# ESP32-Function.net
KiCad netlist of a schematic drawn in EAGLE
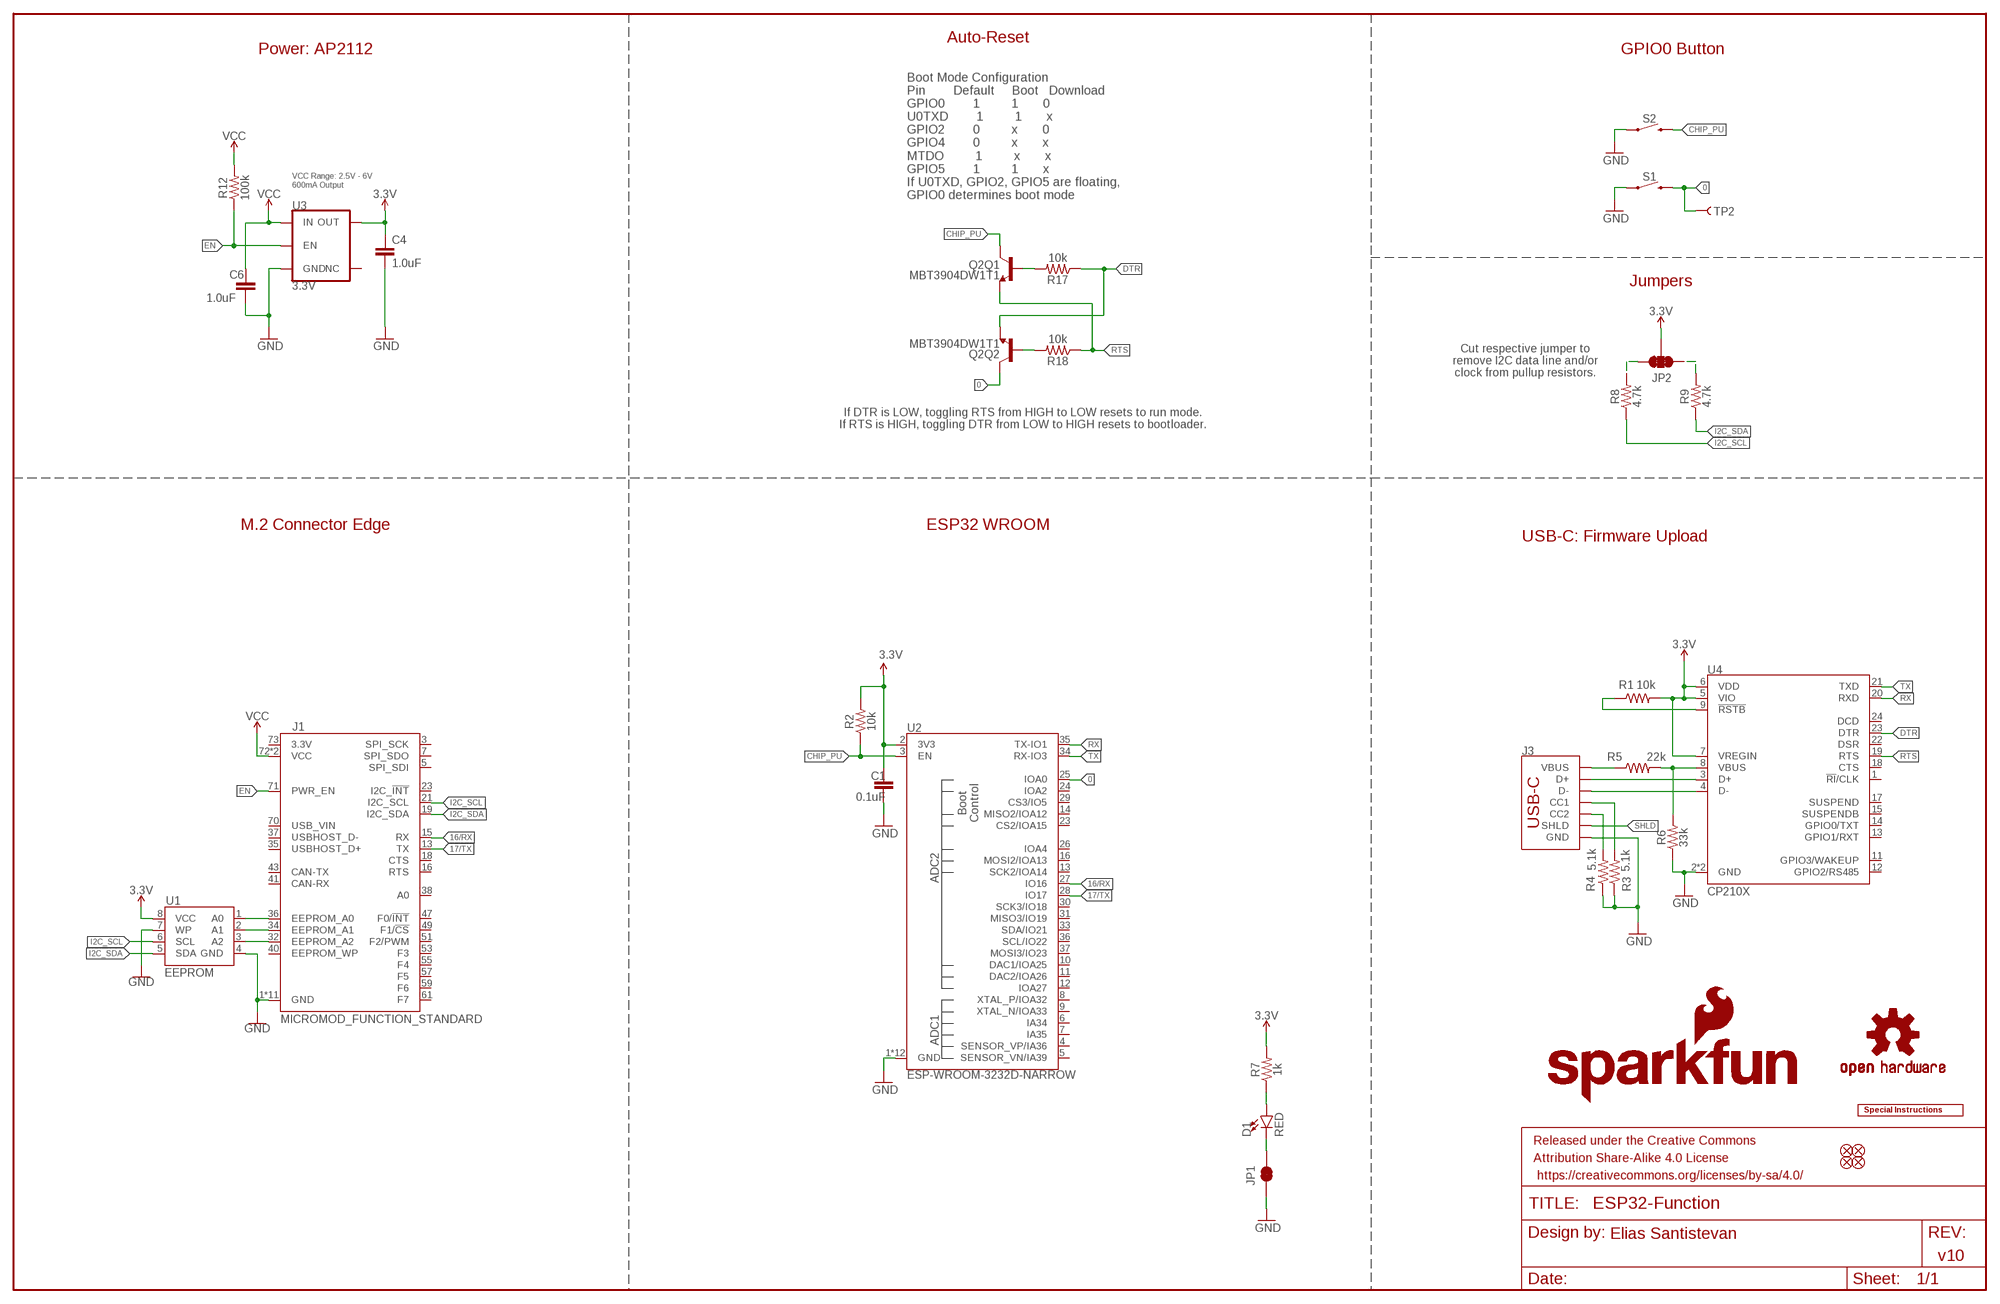
[diagram p0: schematic, sheet 1]

(export (version "E")
  (design (tool "Eeschema 10.0.6"))
  (components
    (comp (ref "C1")
      (value "0.1uF")
      (footprint "eagle-import:0603")
      (libsource (lib "eagle-import") (part "0.1UF-0603-25V-(+80/-20%)"))
    )
    (comp (ref "C4")
      (value "1.0uF")
      (footprint "eagle-import:0603")
      (libsource (lib "eagle-import") (part "1.0UF-0603-16V-10%"))
    )
    (comp (ref "C6")
      (value "1.0uF")
      (footprint "eagle-import:0603")
      (libsource (lib "eagle-import") (part "1.0UF-0603-16V-10%"))
    )
    (comp (ref "D1")
      (value "RED")
      (footprint "eagle-import:LED-0603")
      (libsource (lib "eagle-import") (part "LED-RED0603"))
    )
    (comp (ref "FD1")
      (value "FIDUCIAL1X2")
      (footprint "eagle-import:FIDUCIAL-1X2")
      (libsource (lib "eagle-import") (part "FIDUCIAL1X2"))
    )
    (comp (ref "FD2")
      (value "FIDUCIAL1X2")
      (footprint "eagle-import:FIDUCIAL-1X2")
      (libsource (lib "eagle-import") (part "FIDUCIAL1X2"))
    )
    (comp (ref "FD3")
      (value "FIDUCIAL1X2")
      (footprint "eagle-import:FIDUCIAL-1X2")
      (libsource (lib "eagle-import") (part "FIDUCIAL1X2"))
    )
    (comp (ref "FD4")
      (value "FIDUCIAL1X2")
      (footprint "eagle-import:FIDUCIAL-1X2")
      (libsource (lib "eagle-import") (part "FIDUCIAL1X2"))
    )
    (comp (ref "FRAME2")
      (value "FRAME-LEDGER")
      (footprint "eagle-import:CREATIVE_COMMONS")
      (libsource (lib "eagle-import") (part "FRAME-LEDGER"))
    )
    (comp (ref "J1")
      (value "MICROMOD_FUNCTION_STANDARD")
      (footprint "eagle-import:M.2-CARD-E-22_FUNCTION_STANDARD")
      (libsource (lib "eagle-import") (part "MICROMOD_FUNCTION_STANDARD"))
    )
    (comp (ref "J3")
      (value "USB_C_2-LAYER_PADS")
      (footprint "eagle-import:USB-C-16P-2LAYER-PADS")
      (libsource (lib "eagle-import") (part "USB_C_2-LAYER_PADS"))
    )
    (comp (ref "JP1")
      (value "JUMPER-SMT_2_NC_TRACE_SILK")
      (footprint "eagle-import:SMT-JUMPER_2_NC_TRACE_SILK")
      (libsource (lib "eagle-import") (part "JUMPER-SMT_2_NC_TRACE_SILK"))
    )
    (comp (ref "JP2")
      (value "JUMPER-SMT_3_2-NC_TRACE_SILK")
      (footprint "eagle-import:SMT-JUMPER_3_2-NC_TRACE_SILK")
      (libsource (lib "eagle-import") (part "JUMPER-SMT_3_2-NC_TRACE_SILK"))
    )
    (comp (ref "LOGO1")
      (value "SPECIAL_INSTRUCTIONS-ORDERING")
      (footprint "eagle-import:ORDERING_INSTRUCTIONS")
      (libsource (lib "eagle-import") (part "SPECIAL_INSTRUCTIONS-ORDERING"))
    )
    (comp (ref "LOGO2")
      (value "SFE_LOGO_NAME_FLAME.2_INCH")
      (footprint "eagle-import:SFE_LOGO_NAME_FLAME_.2")
      (libsource (lib "eagle-import") (part "SFE_LOGO_NAME_FLAME.2_INCH"))
    )
    (comp (ref "LOGO3")
      (value "OSHW-LOGOS")
      (footprint "eagle-import:OSHW-LOGO-S")
      (libsource (lib "eagle-import") (part "OSHW-LOGOS"))
    )
    (comp (ref "Q2")
      (value "MBT3904DW1T1")
      (footprint "eagle-import:SC70-6")
      (libsource (lib "eagle-import") (part "TRANS_NPN_DUAL-MBT3904DW1T1"))
    )
    (comp (ref "R1")
      (value "10k")
      (footprint "eagle-import:0603")
      (libsource (lib "eagle-import") (part "10KOHM-0603-1/10W-1%"))
    )
    (comp (ref "R2")
      (value "10k")
      (footprint "eagle-import:0603")
      (libsource (lib "eagle-import") (part "10KOHM-0603-1/10W-1%"))
    )
    (comp (ref "R3")
      (value "5.1k")
      (footprint "eagle-import:0603")
      (libsource (lib "eagle-import") (part "5.1KOHM5.1KOHM-0603-1/10W-1%"))
    )
    (comp (ref "R4")
      (value "5.1k")
      (footprint "eagle-import:0603")
      (libsource (lib "eagle-import") (part "5.1KOHM5.1KOHM-0603-1/10W-1%"))
    )
    (comp (ref "R5")
      (value "22k")
      (footprint "eagle-import:0603")
      (libsource (lib "eagle-import") (part "22KOHM-0603-1/10W-1%"))
    )
    (comp (ref "R6")
      (value "33k")
      (footprint "eagle-import:0603")
      (libsource (lib "eagle-import") (part "33KOHM-0603-1/10W-1%"))
    )
    (comp (ref "R7")
      (value "1k")
      (footprint "eagle-import:0603")
      (libsource (lib "eagle-import") (part "1KOHM-0603-1/10W-1%"))
    )
    (comp (ref "R8")
      (value "4.7k")
      (footprint "eagle-import:0603")
      (libsource (lib "eagle-import") (part "4.7KOHM-0603-1/10W-1%"))
    )
    (comp (ref "R9")
      (value "4.7k")
      (footprint "eagle-import:0603")
      (libsource (lib "eagle-import") (part "4.7KOHM-0603-1/10W-1%"))
    )
    (comp (ref "R12")
      (value "100k")
      (footprint "eagle-import:0603")
      (libsource (lib "eagle-import") (part "100KOHM-0603-1/10W-1%"))
    )
    (comp (ref "R17")
      (value "10k")
      (footprint "eagle-import:0603")
      (libsource (lib "eagle-import") (part "10KOHM-0603-1/10W-1%"))
    )
    (comp (ref "R18")
      (value "10k")
      (footprint "eagle-import:0603")
      (libsource (lib "eagle-import") (part "10KOHM-0603-1/10W-1%"))
    )
    (comp (ref "S1")
      (value "MOMENTARY-SWITCH-SPST-SMD-5.2MM-TALL")
      (footprint "eagle-import:TACTILE_SWITCH_SMD_5.2MM")
      (libsource (lib "eagle-import") (part "MOMENTARY-SWITCH-SPST-SMD-5.2MM-TALL"))
    )
    (comp (ref "S2")
      (value "MOMENTARY-SWITCH-SPST-SMD-5.2MM-TALL")
      (footprint "eagle-import:TACTILE_SWITCH_SMD_5.2MM")
      (libsource (lib "eagle-import") (part "MOMENTARY-SWITCH-SPST-SMD-5.2MM-TALL"))
    )
    (comp (ref "TP2")
      (value "TEST-POINTTP_15TH_THRU")
      (footprint "eagle-import:TP_15TH")
      (libsource (lib "eagle-import") (part "TEST-POINTTP_15TH_THRU"))
    )
    (comp (ref "U1")
      (value "EEPROM")
      (footprint "eagle-import:SO08")
      (libsource (lib "eagle-import") (part "EEPROM-I2C512K"))
    )
    (comp (ref "U2")
      (value "ESP-WROOM-3232D-NARROW")
      (footprint "eagle-import:ESP-WROOM-32D-NARROW")
      (libsource (lib "eagle-import") (part "ESP-WROOM-3232D-NARROW"))
    )
    (comp (ref "U3")
      (value "3.3V")
      (footprint "eagle-import:SOT23-5")
      (libsource (lib "eagle-import") (part "V_REG_AP2112K-3.3V"))
    )
    (comp (ref "U4")
      (value "CP210X")
      (footprint "eagle-import:QFN24")
      (libsource (lib "eagle-import") (part "CP2102N"))
    )
  )
  (nets
    (net (code "1") (name "0") (class "Default")
      (node (ref "Q2") (pin "6") (pinfunction "C_6") (pintype "passive"))
      (node (ref "S1") (pin "3") (pinfunction "2_3") (pintype "passive"))
      (node (ref "TP2") (pin "1") (pinfunction "1_1") (pintype "bidirectional"))
      (node (ref "U2") (pin "25") (pinfunction "IOA0_25") (pintype "bidirectional"))
    )
    (net (code "2") (name "3.3V") (class "Default")
      (node (ref "C1") (pin "1") (pinfunction "1_1") (pintype "passive"))
      (node (ref "C4") (pin "1") (pinfunction "1_1") (pintype "passive"))
      (node (ref "JP2") (pin "2") (pinfunction "2_2") (pintype "passive"))
      (node (ref "R1") (pin "2") (pinfunction "2_2") (pintype "passive"))
      (node (ref "R2") (pin "2") (pinfunction "2_2") (pintype "passive"))
      (node (ref "R7") (pin "2") (pinfunction "2_2") (pintype "passive"))
      (node (ref "U1") (pin "8") (pinfunction "VCC_8") (pintype "power_in"))
      (node (ref "U2") (pin "2") (pinfunction "3V3_2") (pintype "bidirectional"))
      (node (ref "U3") (pin "5") (pinfunction "OUT_5") (pintype "passive"))
      (node (ref "U4") (pin "5") (pinfunction "VIO_5") (pintype "bidirectional"))
      (node (ref "U4") (pin "6") (pinfunction "VDD_6") (pintype "bidirectional"))
      (node (ref "U4") (pin "7") (pinfunction "VREGIN_7") (pintype "bidirectional"))
    )
    (net (code "3") (name "16{slash}RX") (class "Default")
      (node (ref "J1") (pin "15") (pinfunction "RX_15") (pintype "bidirectional"))
      (node (ref "U2") (pin "27") (pinfunction "IO16_27") (pintype "bidirectional"))
    )
    (net (code "4") (name "17{slash}TX") (class "Default")
      (node (ref "J1") (pin "13") (pinfunction "TX_13") (pintype "bidirectional"))
      (node (ref "U2") (pin "28") (pinfunction "IO17_28") (pintype "bidirectional"))
    )
    (net (code "5") (name "CHIP_PU") (class "Default")
      (node (ref "Q2") (pin "3") (pinfunction "C_3") (pintype "passive"))
      (node (ref "R2") (pin "1") (pinfunction "1_1") (pintype "passive"))
      (node (ref "S2") (pin "3") (pinfunction "2_3") (pintype "passive"))
      (node (ref "U2") (pin "3") (pinfunction "EN_3") (pintype "bidirectional"))
    )
    (net (code "6") (name "DTR") (class "Default")
      (node (ref "Q2") (pin "1") (pinfunction "E_1") (pintype "passive"))
      (node (ref "R17") (pin "1") (pinfunction "1_1") (pintype "passive"))
      (node (ref "U4") (pin "23") (pinfunction "DTR_23") (pintype "bidirectional"))
    )
    (net (code "7") (name "EN") (class "Default")
      (node (ref "J1") (pin "71") (pinfunction "PWR_EN_71") (pintype "bidirectional"))
      (node (ref "R12") (pin "1") (pinfunction "1_1") (pintype "passive"))
      (node (ref "U3") (pin "3") (pinfunction "EN_3") (pintype "input"))
    )
    (net (code "8") (name "GND") (class "Default")
      (node (ref "C1") (pin "2") (pinfunction "2_2") (pintype "passive"))
      (node (ref "C4") (pin "2") (pinfunction "2_2") (pintype "passive"))
      (node (ref "C6") (pin "2") (pinfunction "2_2") (pintype "passive"))
      (node (ref "J1") (pin "1") (pinfunction "GND_1") (pintype "bidirectional"))
      (node (ref "J1") (pin "33") (pinfunction "GND_33") (pintype "bidirectional"))
      (node (ref "J1") (pin "39") (pinfunction "GND_39") (pintype "bidirectional"))
      (node (ref "J1") (pin "45") (pinfunction "GND_45") (pintype "bidirectional"))
      (node (ref "J1") (pin "75") (pinfunction "GND_75") (pintype "bidirectional"))
      (node (ref "J1") (pin "GND1") (pinfunction "GND_GND1") (pintype "bidirectional"))
      (node (ref "J1") (pin "GND2") (pinfunction "GND_GND2") (pintype "bidirectional"))
      (node (ref "J1") (pin "GND3") (pinfunction "GND_GND3") (pintype "bidirectional"))
      (node (ref "J1") (pin "GND4") (pinfunction "GND_GND4") (pintype "bidirectional"))
      (node (ref "J1") (pin "GND5") (pinfunction "GND_GND5") (pintype "bidirectional"))
      (node (ref "J1") (pin "GND6") (pinfunction "GND_GND6") (pintype "bidirectional"))
      (node (ref "J3") (pin "GND") (pinfunction "GND_GND") (pintype "bidirectional"))
      (node (ref "J3") (pin "GND2") (pinfunction "GND_GND2") (pintype "bidirectional"))
      (node (ref "JP1") (pin "1") (pinfunction "1_1") (pintype "passive"))
      (node (ref "R3") (pin "1") (pinfunction "1_1") (pintype "passive"))
      (node (ref "R4") (pin "1") (pinfunction "1_1") (pintype "passive"))
      (node (ref "R6") (pin "1") (pinfunction "1_1") (pintype "passive"))
      (node (ref "S1") (pin "1") (pinfunction "1_1") (pintype "passive"))
      (node (ref "S2") (pin "1") (pinfunction "1_1") (pintype "passive"))
      (node (ref "U1") (pin "4") (pinfunction "GND_4") (pintype "power_in"))
      (node (ref "U1") (pin "7") (pinfunction "WP_7") (pintype "bidirectional"))
      (node (ref "U2") (pin "1") (pinfunction "GND_1") (pintype "bidirectional"))
      (node (ref "U2") (pin "15") (pinfunction "GND_15") (pintype "bidirectional"))
      (node (ref "U2") (pin "38") (pinfunction "GND_38") (pintype "bidirectional"))
      (node (ref "U2") (pin "GND1") (pinfunction "GND_GND1") (pintype "bidirectional"))
      (node (ref "U2") (pin "GNDT1") (pinfunction "GND_GNDT1") (pintype "bidirectional"))
      (node (ref "U2") (pin "GNDT2") (pinfunction "GND_GNDT2") (pintype "bidirectional"))
      (node (ref "U2") (pin "GNDT3") (pinfunction "GND_GNDT3") (pintype "bidirectional"))
      (node (ref "U2") (pin "GNDT4") (pinfunction "GND_GNDT4") (pintype "bidirectional"))
      (node (ref "U2") (pin "GNDT5") (pinfunction "GND_GNDT5") (pintype "bidirectional"))
      (node (ref "U2") (pin "GNDT6") (pinfunction "GND_GNDT6") (pintype "bidirectional"))
      (node (ref "U2") (pin "GNDT7") (pinfunction "GND_GNDT7") (pintype "bidirectional"))
      (node (ref "U2") (pin "GNDT8") (pinfunction "GND_GNDT8") (pintype "bidirectional"))
      (node (ref "U3") (pin "2") (pinfunction "GND_2") (pintype "input"))
      (node (ref "U4") (pin "2") (pinfunction "GND_2") (pintype "bidirectional"))
      (node (ref "U4") (pin "PAD") (pinfunction "GND_PAD") (pintype "bidirectional"))
    )
    (net (code "9") (name "I2C_SCL") (class "Default")
      (node (ref "J1") (pin "21") (pinfunction "I2C_SCL_21") (pintype "bidirectional"))
      (node (ref "R8") (pin "1") (pinfunction "1_1") (pintype "passive"))
      (node (ref "U1") (pin "6") (pinfunction "SCL_6") (pintype "bidirectional"))
    )
    (net (code "10") (name "I2C_SDA") (class "Default")
      (node (ref "J1") (pin "19") (pinfunction "I2C_SDA_19") (pintype "bidirectional"))
      (node (ref "R9") (pin "1") (pinfunction "1_1") (pintype "passive"))
      (node (ref "U1") (pin "5") (pinfunction "SDA_5") (pintype "bidirectional"))
    )
    (net (code "11") (name "Net-(D1-PadA)") (class "Default")
      (node (ref "D1") (pin "A") (pinfunction "A_A") (pintype "passive"))
      (node (ref "R7") (pin "1") (pinfunction "1_1") (pintype "passive"))
    )
    (net (code "12") (name "Net-(D1-PadC)") (class "Default")
      (node (ref "D1") (pin "C") (pinfunction "C_C") (pintype "passive"))
      (node (ref "JP1") (pin "2") (pinfunction "2_2") (pintype "passive"))
    )
    (net (code "13") (name "Net-(J1-EEPROM_A0)") (class "Default")
      (node (ref "J1") (pin "36") (pinfunction "EEPROM_A0_36") (pintype "bidirectional"))
      (node (ref "U1") (pin "1") (pinfunction "A0_1") (pintype "bidirectional"))
    )
    (net (code "14") (name "Net-(J1-EEPROM_A1)") (class "Default")
      (node (ref "J1") (pin "34") (pinfunction "EEPROM_A1_34") (pintype "bidirectional"))
      (node (ref "U1") (pin "2") (pinfunction "A1_2") (pintype "bidirectional"))
    )
    (net (code "15") (name "Net-(J1-EEPROM_A2)") (class "Default")
      (node (ref "J1") (pin "32") (pinfunction "EEPROM_A2_32") (pintype "bidirectional"))
      (node (ref "U1") (pin "3") (pinfunction "A2_3") (pintype "bidirectional"))
    )
    (net (code "16") (name "Net-(J3-CC1)") (class "Default")
      (node (ref "J3") (pin "A5") (pinfunction "CC1_A5") (pintype "bidirectional"))
      (node (ref "R3") (pin "2") (pinfunction "2_2") (pintype "passive"))
    )
    (net (code "17") (name "Net-(J3-CC2)") (class "Default")
      (node (ref "J3") (pin "B5") (pinfunction "CC2_B5") (pintype "bidirectional"))
      (node (ref "R4") (pin "2") (pinfunction "2_2") (pintype "passive"))
    )
    (net (code "18") (name "Net-(J3-VBUS-PadVBUS1)") (class "Default")
      (node (ref "J3") (pin "VBUS1") (pinfunction "VBUS_VBUS1") (pintype "bidirectional"))
      (node (ref "J3") (pin "VBUS2") (pinfunction "VBUS_VBUS2") (pintype "bidirectional"))
      (node (ref "R5") (pin "1") (pinfunction "1_1") (pintype "passive"))
    )
    (net (code "19") (name "Net-(JP2-Pad1)") (class "Default")
      (node (ref "JP2") (pin "1") (pinfunction "1_1") (pintype "passive"))
      (node (ref "R9") (pin "2") (pinfunction "2_2") (pintype "passive"))
    )
    (net (code "20") (name "Net-(JP2-Pad3)") (class "Default")
      (node (ref "JP2") (pin "3") (pinfunction "3_3") (pintype "passive"))
      (node (ref "R8") (pin "2") (pinfunction "2_2") (pintype "passive"))
    )
    (net (code "21") (name "Net-(Q2A-B)") (class "Default")
      (node (ref "Q2") (pin "5") (pinfunction "B_5") (pintype "passive"))
      (node (ref "R17") (pin "2") (pinfunction "2_2") (pintype "passive"))
    )
    (net (code "22") (name "Net-(Q2B-B)") (class "Default")
      (node (ref "Q2") (pin "2") (pinfunction "B_2") (pintype "passive"))
      (node (ref "R18") (pin "2") (pinfunction "2_2") (pintype "passive"))
    )
    (net (code "23") (name "Net-(U4-D+)") (class "Default")
      (node (ref "J3") (pin "A6") (pinfunction "D+_A6") (pintype "bidirectional"))
      (node (ref "J3") (pin "B6") (pinfunction "D+_B6") (pintype "bidirectional"))
      (node (ref "U4") (pin "3") (pinfunction "D+_3") (pintype "bidirectional"))
    )
    (net (code "24") (name "Net-(U4-D-)") (class "Default")
      (node (ref "J3") (pin "A7") (pinfunction "D-_A7") (pintype "bidirectional"))
      (node (ref "J3") (pin "B7") (pinfunction "D-_B7") (pintype "bidirectional"))
      (node (ref "U4") (pin "4") (pinfunction "D-_4") (pintype "bidirectional"))
    )
    (net (code "25") (name "Net-(U4-VBUS)") (class "Default")
      (node (ref "R5") (pin "2") (pinfunction "2_2") (pintype "passive"))
      (node (ref "R6") (pin "2") (pinfunction "2_2") (pintype "passive"))
      (node (ref "U4") (pin "8") (pinfunction "VBUS_8") (pintype "bidirectional"))
    )
    (net (code "26") (name "Net-(U4-~{RSTB})") (class "Default")
      (node (ref "R1") (pin "1") (pinfunction "1_1") (pintype "passive"))
      (node (ref "U4") (pin "9") (pinfunction "~{RSTB}_9") (pintype "bidirectional"))
    )
    (net (code "27") (name "RTS") (class "Default")
      (node (ref "Q2") (pin "4") (pinfunction "E_4") (pintype "passive"))
      (node (ref "R18") (pin "1") (pinfunction "1_1") (pintype "passive"))
      (node (ref "U4") (pin "19") (pinfunction "RTS_19") (pintype "bidirectional"))
    )
    (net (code "28") (name "RX") (class "Default")
      (node (ref "U2") (pin "35") (pinfunction "TX-IO1_35") (pintype "bidirectional"))
      (node (ref "U4") (pin "20") (pinfunction "RXD_20") (pintype "bidirectional"))
    )
    (net (code "29") (name "SHLD") (class "Default")
      (node (ref "J3") (pin "SHLD1") (pinfunction "SHLD_SHLD1") (pintype "bidirectional"))
      (node (ref "J3") (pin "SHLD2") (pinfunction "SHLD_SHLD2") (pintype "bidirectional"))
      (node (ref "J3") (pin "SHLD3") (pinfunction "SHLD_SHLD3") (pintype "bidirectional"))
      (node (ref "J3") (pin "SHLD4") (pinfunction "SHLD_SHLD4") (pintype "bidirectional"))
    )
    (net (code "30") (name "TX") (class "Default")
      (node (ref "U2") (pin "34") (pinfunction "RX-IO3_34") (pintype "bidirectional"))
      (node (ref "U4") (pin "21") (pinfunction "TXD_21") (pintype "bidirectional"))
    )
    (net (code "31") (name "VCC") (class "Default")
      (node (ref "C6") (pin "1") (pinfunction "1_1") (pintype "passive"))
      (node (ref "J1") (pin "72") (pinfunction "VCC_72") (pintype "bidirectional"))
      (node (ref "J1") (pin "74") (pinfunction "VCC_74") (pintype "bidirectional"))
      (node (ref "R12") (pin "2") (pinfunction "2_2") (pintype "passive"))
      (node (ref "U3") (pin "1") (pinfunction "IN_1") (pintype "input"))
    )
    (net (code "32") (name "unconnected-(J1-3.3V-Pad73)") (class "Default")
      (node (ref "J1") (pin "73") (pinfunction "3.3V_73") (pintype "bidirectional"))
    )
    (net (code "33") (name "unconnected-(J1-A0-Pad38)") (class "Default")
      (node (ref "J1") (pin "38") (pinfunction "A0_38") (pintype "bidirectional"))
    )
    (net (code "34") (name "unconnected-(J1-CAN-RX-Pad41)") (class "Default")
      (node (ref "J1") (pin "41") (pinfunction "CAN-RX_41") (pintype "bidirectional"))
    )
    (net (code "35") (name "unconnected-(J1-CAN-TX-Pad43)") (class "Default")
      (node (ref "J1") (pin "43") (pinfunction "CAN-TX_43") (pintype "bidirectional"))
    )
    (net (code "36") (name "unconnected-(J1-CTS-Pad18)") (class "Default")
      (node (ref "J1") (pin "18") (pinfunction "CTS_18") (pintype "bidirectional"))
    )
    (net (code "37") (name "unconnected-(J1-EEPROM_WP-Pad40)") (class "Default")
      (node (ref "J1") (pin "40") (pinfunction "EEPROM_WP_40") (pintype "bidirectional"))
    )
    (net (code "38") (name "unconnected-(J1-F0{slash}~{INT}-Pad47)") (class "Default")
      (node (ref "J1") (pin "47") (pinfunction "F0/~{INT}_47") (pintype "bidirectional"))
    )
    (net (code "39") (name "unconnected-(J1-F1{slash}~{CS}-Pad49)") (class "Default")
      (node (ref "J1") (pin "49") (pinfunction "F1/~{CS}_49") (pintype "bidirectional"))
    )
    (net (code "40") (name "unconnected-(J1-F2{slash}PWM-Pad51)") (class "Default")
      (node (ref "J1") (pin "51") (pinfunction "F2/PWM_51") (pintype "bidirectional"))
    )
    (net (code "41") (name "unconnected-(J1-F3-Pad53)") (class "Default")
      (node (ref "J1") (pin "53") (pinfunction "F3_53") (pintype "bidirectional"))
    )
    (net (code "42") (name "unconnected-(J1-F4-Pad55)") (class "Default")
      (node (ref "J1") (pin "55") (pinfunction "F4_55") (pintype "bidirectional"))
    )
    (net (code "43") (name "unconnected-(J1-F5-Pad57)") (class "Default")
      (node (ref "J1") (pin "57") (pinfunction "F5_57") (pintype "bidirectional"))
    )
    (net (code "44") (name "unconnected-(J1-F6-Pad59)") (class "Default")
      (node (ref "J1") (pin "59") (pinfunction "F6_59") (pintype "bidirectional"))
    )
    (net (code "45") (name "unconnected-(J1-F7-Pad61)") (class "Default")
      (node (ref "J1") (pin "61") (pinfunction "F7_61") (pintype "bidirectional"))
    )
    (net (code "46") (name "unconnected-(J1-I2C_~{INT}-Pad23)") (class "Default")
      (node (ref "J1") (pin "23") (pinfunction "I2C_~{INT}_23") (pintype "bidirectional"))
    )
    (net (code "47") (name "unconnected-(J1-RTS-Pad16)") (class "Default")
      (node (ref "J1") (pin "16") (pinfunction "RTS_16") (pintype "bidirectional"))
    )
    (net (code "48") (name "unconnected-(J1-SPI_SCK-Pad3)") (class "Default")
      (node (ref "J1") (pin "3") (pinfunction "SPI_SCK_3") (pintype "bidirectional"))
    )
    (net (code "49") (name "unconnected-(J1-SPI_SDI-Pad5)") (class "Default")
      (node (ref "J1") (pin "5") (pinfunction "SPI_SDI_5") (pintype "bidirectional"))
    )
    (net (code "50") (name "unconnected-(J1-SPI_SDO-Pad7)") (class "Default")
      (node (ref "J1") (pin "7") (pinfunction "SPI_SDO_7") (pintype "bidirectional"))
    )
    (net (code "51") (name "unconnected-(J1-USBHOST_D+-Pad35)") (class "Default")
      (node (ref "J1") (pin "35") (pinfunction "USBHOST_D+_35") (pintype "bidirectional"))
    )
    (net (code "52") (name "unconnected-(J1-USBHOST_D--Pad37)") (class "Default")
      (node (ref "J1") (pin "37") (pinfunction "USBHOST_D-_37") (pintype "bidirectional"))
    )
    (net (code "53") (name "unconnected-(J1-USB_VIN-Pad70)") (class "Default")
      (node (ref "J1") (pin "70") (pinfunction "USB_VIN_70") (pintype "bidirectional"))
    )
    (net (code "54") (name "unconnected-(U2-CS2{slash}IOA15-Pad23)") (class "Default")
      (node (ref "U2") (pin "23") (pinfunction "CS2/IOA15_23") (pintype "bidirectional"))
    )
    (net (code "55") (name "unconnected-(U2-CS3{slash}IO5-Pad29)") (class "Default")
      (node (ref "U2") (pin "29") (pinfunction "CS3/IO5_29") (pintype "bidirectional"))
    )
    (net (code "56") (name "unconnected-(U2-DAC1{slash}IOA25-Pad10)") (class "Default")
      (node (ref "U2") (pin "10") (pinfunction "DAC1/IOA25_10") (pintype "bidirectional"))
    )
    (net (code "57") (name "unconnected-(U2-DAC2{slash}IOA26-Pad11)") (class "Default")
      (node (ref "U2") (pin "11") (pinfunction "DAC2/IOA26_11") (pintype "bidirectional"))
    )
    (net (code "58") (name "unconnected-(U2-IA34-Pad6)") (class "Default")
      (node (ref "U2") (pin "6") (pinfunction "IA34_6") (pintype "bidirectional"))
    )
    (net (code "59") (name "unconnected-(U2-IA35-Pad7)") (class "Default")
      (node (ref "U2") (pin "7") (pinfunction "IA35_7") (pintype "bidirectional"))
    )
    (net (code "60") (name "unconnected-(U2-IOA2-Pad24)") (class "Default")
      (node (ref "U2") (pin "24") (pinfunction "IOA2_24") (pintype "bidirectional"))
    )
    (net (code "61") (name "unconnected-(U2-IOA4-Pad26)") (class "Default")
      (node (ref "U2") (pin "26") (pinfunction "IOA4_26") (pintype "bidirectional"))
    )
    (net (code "62") (name "unconnected-(U2-IOA27-Pad12)") (class "Default")
      (node (ref "U2") (pin "12") (pinfunction "IOA27_12") (pintype "bidirectional"))
    )
    (net (code "63") (name "unconnected-(U2-MISO2{slash}IOA12-Pad14)") (class "Default")
      (node (ref "U2") (pin "14") (pinfunction "MISO2/IOA12_14") (pintype "bidirectional"))
    )
    (net (code "64") (name "unconnected-(U2-MISO3{slash}IO19-Pad31)") (class "Default")
      (node (ref "U2") (pin "31") (pinfunction "MISO3/IO19_31") (pintype "bidirectional"))
    )
    (net (code "65") (name "unconnected-(U2-MOSI2{slash}IOA13-Pad16)") (class "Default")
      (node (ref "U2") (pin "16") (pinfunction "MOSI2/IOA13_16") (pintype "bidirectional"))
    )
    (net (code "66") (name "unconnected-(U2-MOSI3{slash}IO23-Pad37)") (class "Default")
      (node (ref "U2") (pin "37") (pinfunction "MOSI3/IO23_37") (pintype "bidirectional"))
    )
    (net (code "67") (name "unconnected-(U2-SCK2{slash}IOA14-Pad13)") (class "Default")
      (node (ref "U2") (pin "13") (pinfunction "SCK2/IOA14_13") (pintype "bidirectional"))
    )
    (net (code "68") (name "unconnected-(U2-SCK3{slash}IO18-Pad30)") (class "Default")
      (node (ref "U2") (pin "30") (pinfunction "SCK3/IO18_30") (pintype "bidirectional"))
    )
    (net (code "69") (name "unconnected-(U2-SCL{slash}IO22-Pad36)") (class "Default")
      (node (ref "U2") (pin "36") (pinfunction "SCL/IO22_36") (pintype "bidirectional"))
    )
    (net (code "70") (name "unconnected-(U2-SDA{slash}IO21-Pad33)") (class "Default")
      (node (ref "U2") (pin "33") (pinfunction "SDA/IO21_33") (pintype "bidirectional"))
    )
    (net (code "71") (name "unconnected-(U2-SENSOR_VN{slash}IA39-Pad5)") (class "Default")
      (node (ref "U2") (pin "5") (pinfunction "SENSOR_VN/IA39_5") (pintype "bidirectional"))
    )
    (net (code "72") (name "unconnected-(U2-SENSOR_VP{slash}IA36-Pad4)") (class "Default")
      (node (ref "U2") (pin "4") (pinfunction "SENSOR_VP/IA36_4") (pintype "bidirectional"))
    )
    (net (code "73") (name "unconnected-(U2-XTAL_N{slash}IOA33-Pad9)") (class "Default")
      (node (ref "U2") (pin "9") (pinfunction "XTAL_N/IOA33_9") (pintype "bidirectional"))
    )
    (net (code "74") (name "unconnected-(U2-XTAL_P{slash}IOA32-Pad8)") (class "Default")
      (node (ref "U2") (pin "8") (pinfunction "XTAL_P/IOA32_8") (pintype "bidirectional"))
    )
    (net (code "75") (name "unconnected-(U3-NC-Pad4)") (class "Default")
      (node (ref "U3") (pin "4") (pinfunction "NC_4") (pintype "no_connect"))
    )
    (net (code "76") (name "unconnected-(U4-CTS-Pad18)") (class "Default")
      (node (ref "U4") (pin "18") (pinfunction "CTS_18") (pintype "bidirectional"))
    )
    (net (code "77") (name "unconnected-(U4-DCD-Pad24)") (class "Default")
      (node (ref "U4") (pin "24") (pinfunction "DCD_24") (pintype "bidirectional"))
    )
    (net (code "78") (name "unconnected-(U4-DSR-Pad22)") (class "Default")
      (node (ref "U4") (pin "22") (pinfunction "DSR_22") (pintype "bidirectional"))
    )
    (net (code "79") (name "unconnected-(U4-GPIO0{slash}TXT-Pad14)") (class "Default")
      (node (ref "U4") (pin "14") (pinfunction "GPIO0/TXT_14") (pintype "bidirectional"))
    )
    (net (code "80") (name "unconnected-(U4-GPIO1{slash}RXT-Pad13)") (class "Default")
      (node (ref "U4") (pin "13") (pinfunction "GPIO1/RXT_13") (pintype "bidirectional"))
    )
    (net (code "81") (name "unconnected-(U4-GPIO2{slash}RS485-Pad12)") (class "Default")
      (node (ref "U4") (pin "12") (pinfunction "GPIO2/RS485_12") (pintype "bidirectional"))
    )
    (net (code "82") (name "unconnected-(U4-GPIO3{slash}WAKEUP-Pad11)") (class "Default")
      (node (ref "U4") (pin "11") (pinfunction "GPIO3/WAKEUP_11") (pintype "bidirectional"))
    )
    (net (code "83") (name "unconnected-(U4-SUSPEND-Pad17)") (class "Default")
      (node (ref "U4") (pin "17") (pinfunction "SUSPEND_17") (pintype "bidirectional"))
    )
    (net (code "84") (name "unconnected-(U4-SUSPENDB-Pad15)") (class "Default")
      (node (ref "U4") (pin "15") (pinfunction "SUSPENDB_15") (pintype "bidirectional"))
    )
    (net (code "85") (name "unconnected-(U4-~{RI}{slash}CLK-Pad1)") (class "Default")
      (node (ref "U4") (pin "1") (pinfunction "~{RI}/CLK_1") (pintype "bidirectional"))
    )
  )
)
